# GoPiGo_Proto_10.net
KiCad netlist of a schematic drawn in EAGLE
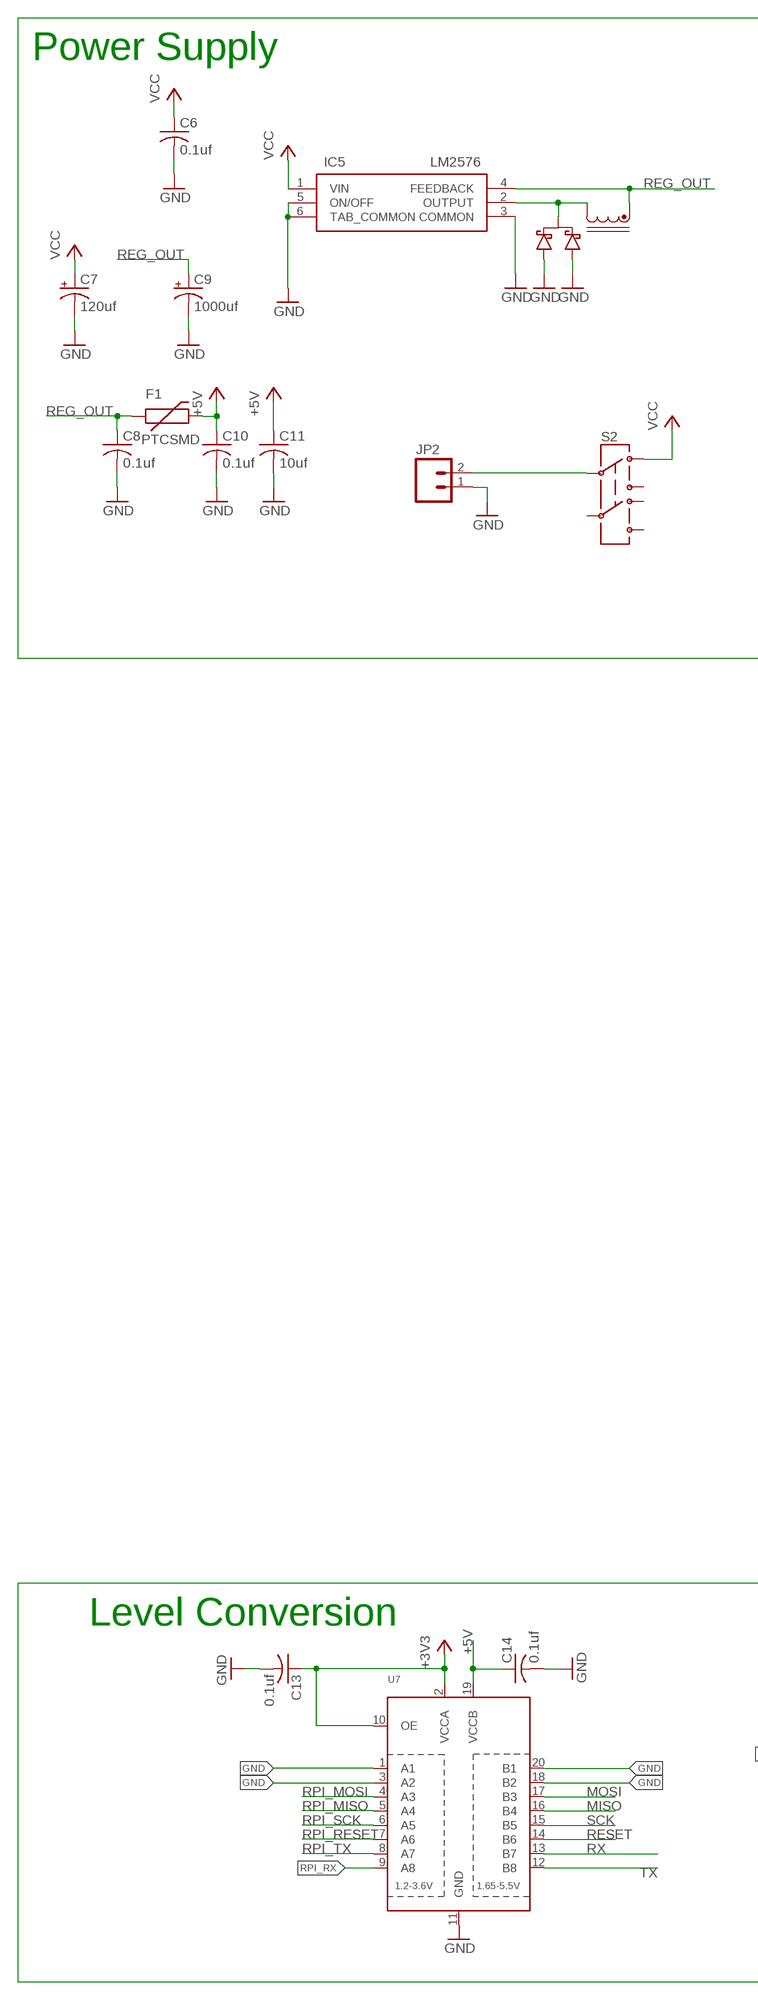
[diagram p0: schematic, sheet 1, part 1 of 2]
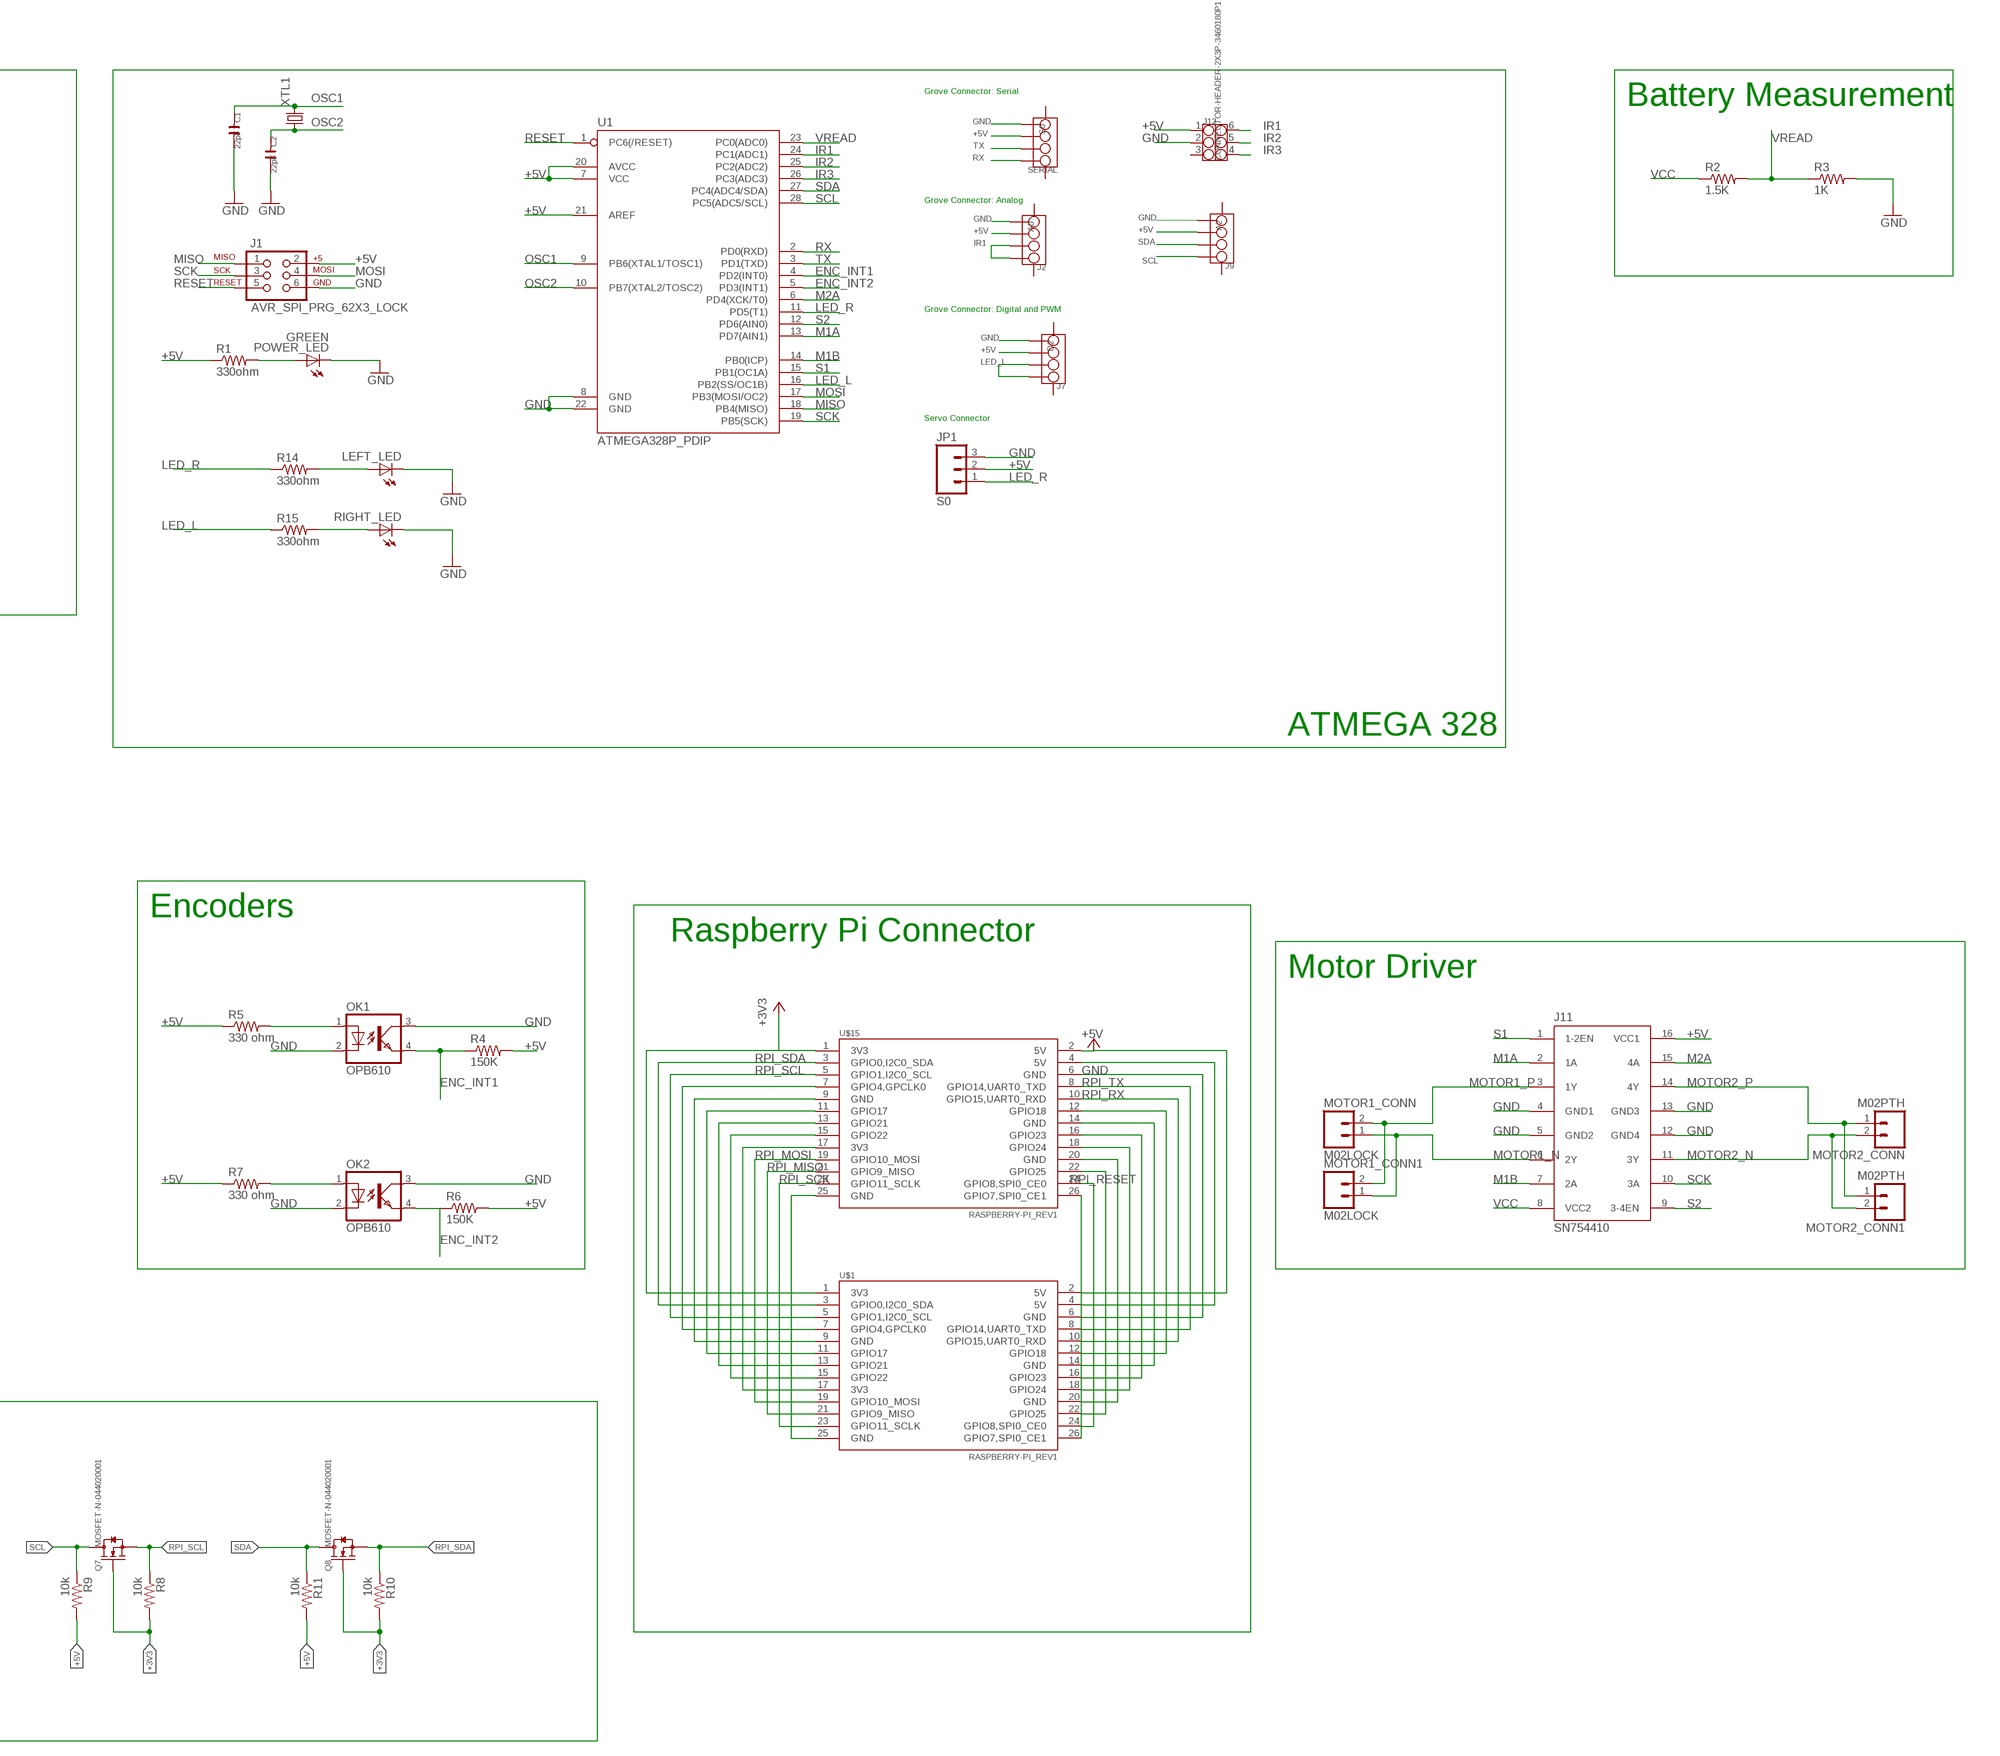
[diagram p1: schematic, sheet 1, part 2 of 2]

(export (version "E")
  (design (tool "Eeschema 10.0.6"))
  (components
    (comp (ref "C1")
      (value "22pF")
      (footprint "eagle-import:C0805")
      (libsource (lib "eagle-import") (part "C-0805"))
    )
    (comp (ref "C2")
      (value "22pF")
      (footprint "eagle-import:C0805")
      (libsource (lib "eagle-import") (part "C-0805"))
    )
    (comp (ref "C6")
      (value "0.1uf")
      (footprint "eagle-import:C0603")
      (libsource (lib "eagle-import") (part "resistor_C-USC0603"))
    )
    (comp (ref "C7")
      (value "120uf")
      (footprint "eagle-import:E2,5-6")
      (libsource (lib "eagle-import") (part "CPOL-USE2.5-6"))
    )
    (comp (ref "C8")
      (value "0.1uf")
      (footprint "eagle-import:C0603")
      (libsource (lib "eagle-import") (part "resistor_C-USC0603"))
    )
    (comp (ref "C9")
      (value "1000uf")
      (footprint "eagle-import:E5-13")
      (libsource (lib "eagle-import") (part "CPOL-USE5-13"))
    )
    (comp (ref "C10")
      (value "0.1uf")
      (footprint "eagle-import:C0603")
      (libsource (lib "eagle-import") (part "resistor_C-USC0603"))
    )
    (comp (ref "C11")
      (value "10uf")
      (footprint "eagle-import:C0805")
      (libsource (lib "eagle-import") (part "C-USC0805"))
    )
    (comp (ref "C13")
      (value "0.1uf")
      (footprint "eagle-import:C0603")
      (libsource (lib "eagle-import") (part "resistor_C-USC0603"))
    )
    (comp (ref "C14")
      (value "0.1uf")
      (footprint "eagle-import:C0603")
      (libsource (lib "eagle-import") (part "resistor_C-USC0603"))
    )
    (comp (ref "D1")
      (value "DIODE_SCHOTTKY_VS-6CWQ04FNTRPBF")
      (footprint "eagle-import:DPAK")
      (libsource (lib "eagle-import") (part "DIODE_SCHOTTKY_VS-6CWQ04FNTRPBF"))
    )
    (comp (ref "F1")
      (value "PTCSMD")
      (footprint "eagle-import:PTC-1206")
      (libsource (lib "eagle-import") (part "PTCSMD"))
    )
    (comp (ref "IC5")
      (value "LM2576")
      (footprint "eagle-import:TO220-5-H")
      (libsource (lib "eagle-import") (part "REGULATOR_SWITCHING_LM2575_LM2576"))
    )
    (comp (ref "J1")
      (value "AVR_SPI_PRG_62X3_LOCK")
      (footprint "eagle-import:2X3_LOCK")
      (libsource (lib "eagle-import") (part "AVR_SPI_PRG_62X3_LOCK"))
    )
    (comp (ref "J2")
      (value "A0")
      (footprint "eagle-import:4P-SMD-2.0-90D")
      (libsource (lib "eagle-import") (part "GROVE-4P-2.0-SMD-FEMALE-REINFORCE-3470120P1"))
    )
    (comp (ref "J7")
      (value "D2")
      (footprint "eagle-import:4P-SMD-2.0-90D")
      (libsource (lib "eagle-import") (part "GROVE-4P-2.0-SMD-FEMALE-REINFORCE-3470120P1"))
    )
    (comp (ref "J9")
      (value "A2")
      (footprint "eagle-import:4P-SMD-2.0-90D")
      (libsource (lib "eagle-import") (part "GROVE-4P-2.0-SMD-FEMALE-REINFORCE-3470120P1"))
    )
    (comp (ref "J11")
      (value "SN754410")
      (footprint "eagle-import:DIL16")
      (fields (field (name "MPN") "L293D"))
      (libsource (lib "eagle-import") (part "L293D"))
    )
    (comp (ref "J12")
      (value "CONNECTOR-HEADER-2X3P-3460180P1")
      (footprint "eagle-import:2X3P-2.54-2.54-11.6-3.0-BLACK-MALE")
      (libsource (lib "eagle-import") (part "CONNECTOR-HEADER-2X3P-3460180P1"))
    )
    (comp (ref "JP1")
      (value "S0")
      (footprint "eagle-import:1X03")
      (libsource (lib "eagle-import") (part "M03PTH"))
    )
    (comp (ref "JP2")
      (value "M02LOCK")
      (footprint "eagle-import:1X02_LOCK")
      (libsource (lib "eagle-import") (part "zz SparkFun_M02LOCK"))
    )
    (comp (ref "LEFT_LED")
      (value "LED5MM")
      (footprint "eagle-import:LED5MM")
      (libsource (lib "eagle-import") (part "LED5MM"))
    )
    (comp (ref "MOTOR1_CONN")
      (value "M02LOCK")
      (footprint "eagle-import:1X02_LOCK")
      (libsource (lib "eagle-import") (part "M02LOCK"))
    )
    (comp (ref "MOTOR1_CONN1")
      (value "M02LOCK")
      (footprint "eagle-import:1X02_LOCK")
      (libsource (lib "eagle-import") (part "M02LOCK"))
    )
    (comp (ref "MOTOR2_CONN")
      (value "M02PTH")
      (footprint "eagle-import:1X02")
      (libsource (lib "eagle-import") (part "M02PTH"))
    )
    (comp (ref "MOTOR2_CONN1")
      (value "M02PTH")
      (footprint "eagle-import:1X02")
      (libsource (lib "eagle-import") (part "M02PTH"))
    )
    (comp (ref "OK1")
      (value "OPB610")
      (footprint "eagle-import:SFH9310")
      (libsource (lib "eagle-import") (part "SFH9310"))
    )
    (comp (ref "OK2")
      (value "OPB610")
      (footprint "eagle-import:SFH9310")
      (libsource (lib "eagle-import") (part "SFH9310"))
    )
    (comp (ref "POWER_LED")
      (value "GREEN")
      (footprint "eagle-import:LED-0603")
      (libsource (lib "eagle-import") (part "LED-GREEN0603"))
    )
    (comp (ref "Q7")
      (value "MOSFET-N-044020001")
      (footprint "eagle-import:SOT23")
      (libsource (lib "eagle-import") (part "MOSFET-N-044020001"))
    )
    (comp (ref "Q8")
      (value "MOSFET-N-044020001")
      (footprint "eagle-import:SOT23")
      (libsource (lib "eagle-import") (part "MOSFET-N-044020001"))
    )
    (comp (ref "R1")
      (value "330ohm")
      (footprint "eagle-import:0603-RES")
      (libsource (lib "eagle-import") (part "RESISTOR0603"))
    )
    (comp (ref "R2")
      (value "1.5K")
      (footprint "eagle-import:0603-RES")
      (libsource (lib "eagle-import") (part "RESISTOR0603"))
    )
    (comp (ref "R3")
      (value "1K")
      (footprint "eagle-import:0603-RES")
      (libsource (lib "eagle-import") (part "RESISTOR0603"))
    )
    (comp (ref "R4")
      (value "150K")
      (footprint "eagle-import:0603-RES")
      (libsource (lib "eagle-import") (part "RESISTOR0603"))
    )
    (comp (ref "R5")
      (value "330 ohm")
      (footprint "eagle-import:0603-RES")
      (libsource (lib "eagle-import") (part "RESISTOR0603"))
    )
    (comp (ref "R6")
      (value "150K")
      (footprint "eagle-import:0603-RES")
      (libsource (lib "eagle-import") (part "RESISTOR0603"))
    )
    (comp (ref "R7")
      (value "330 ohm")
      (footprint "eagle-import:0603-RES")
      (libsource (lib "eagle-import") (part "RESISTOR0603"))
    )
    (comp (ref "R8")
      (value "10k")
      (footprint "eagle-import:0603-RES")
      (libsource (lib "eagle-import") (part "RESISTOR0603"))
    )
    (comp (ref "R9")
      (value "10k")
      (footprint "eagle-import:0603-RES")
      (libsource (lib "eagle-import") (part "RESISTOR0603"))
    )
    (comp (ref "R10")
      (value "10k")
      (footprint "eagle-import:0603-RES")
      (libsource (lib "eagle-import") (part "RESISTOR0603"))
    )
    (comp (ref "R11")
      (value "10k")
      (footprint "eagle-import:0603-RES")
      (libsource (lib "eagle-import") (part "RESISTOR0603"))
    )
    (comp (ref "R14")
      (value "330ohm")
      (footprint "eagle-import:0603-RES")
      (libsource (lib "eagle-import") (part "RESISTOR0603"))
    )
    (comp (ref "R15")
      (value "330ohm")
      (footprint "eagle-import:0603-RES")
      (libsource (lib "eagle-import") (part "RESISTOR0603"))
    )
    (comp (ref "RIGHT_LED")
      (value "LED5MM")
      (footprint "eagle-import:LED5MM")
      (libsource (lib "eagle-import") (part "LED5MM"))
    )
    (comp (ref "S2")
      (value "SWITCH-DPDTOS")
      (footprint "eagle-import:OS")
      (libsource (lib "eagle-import") (part "SWITCH-DPDTOS"))
    )
    (comp (ref "SERIAL")
      (value "S0")
      (footprint "eagle-import:4P-SMD-2.0-90D")
      (libsource (lib "eagle-import") (part "GROVE-4P-2.0-SMD-FEMALE-REINFORCE-3470120P1"))
    )
    (comp (ref "U$1")
      (value "RASPBERRY-PI_REV1")
      (footprint "eagle-import:RASPBERRY-PI_REV1")
      (libsource (lib "eagle-import") (part "RASPBERRY-PI_REV1"))
    )
    (comp (ref "U$14")
      (value "INDUCTOR_PULSE_P0250.XXXNL")
      (footprint "eagle-import:INDUCTOR_PULSE_P0250.XXXNL")
      (libsource (lib "eagle-import") (part "INDUCTOR_PULSE_P0250.XXXNL"))
    )
    (comp (ref "U$15")
      (value "RASPBERRY-PI_REV1")
      (footprint "eagle-import:RASPBERRY-PI_REV1")
      (libsource (lib "eagle-import") (part "RASPBERRY-PI_REV1"))
    )
    (comp (ref "U1")
      (value "ATMEGA328P_PDIP")
      (footprint "eagle-import:DIL28-3")
      (libsource (lib "eagle-import") (part "ATMEGA328P_PDIP"))
    )
    (comp (ref "U7")
      (value "TXB0108PWR")
      (footprint "eagle-import:TSSOP20")
      (libsource (lib "eagle-import") (part "TXB0108PWR"))
    )
    (comp (ref "XTL1")
      (value "CRYSTALHC49S")
      (footprint "eagle-import:HC49_S")
      (libsource (lib "eagle-import") (part "CRYSTALHC49S"))
    )
  )
  (nets
    (net (code "1") (name "+3V3") (class "Default")
      (node (ref "C13") (pin "1") (pinfunction "1_1") (pintype "passive"))
      (node (ref "Q7") (pin "1") (pinfunction "G_1") (pintype "passive"))
      (node (ref "Q8") (pin "1") (pinfunction "G_1") (pintype "passive"))
      (node (ref "R10") (pin "2") (pinfunction "2_2") (pintype "passive"))
      (node (ref "R8") (pin "2") (pinfunction "2_2") (pintype "passive"))
      (node (ref "U$1") (pin "1") (pinfunction "3V3_1") (pintype "bidirectional"))
      (node (ref "U$15") (pin "1") (pinfunction "3V3_1") (pintype "bidirectional"))
      (node (ref "U7") (pin "10") (pinfunction "OE_10") (pintype "bidirectional"))
      (node (ref "U7") (pin "2") (pinfunction "VCCA_2") (pintype "bidirectional"))
    )
    (net (code "2") (name "+5V") (class "Default")
      (node (ref "C10") (pin "1") (pinfunction "1_1") (pintype "passive"))
      (node (ref "C11") (pin "1") (pinfunction "1_1") (pintype "passive"))
      (node (ref "C14") (pin "1") (pinfunction "1_1") (pintype "passive"))
      (node (ref "F1") (pin "2") (pinfunction "2_2") (pintype "bidirectional"))
      (node (ref "J1") (pin "2") (pinfunction "2_2") (pintype "passive"))
      (node (ref "J11") (pin "16") (pinfunction "VCC1_16") (pintype "power_in"))
      (node (ref "J12") (pin "1") (pinfunction "1_1") (pintype "bidirectional"))
      (node (ref "J2") (pin "3") (pinfunction "3_3") (pintype "bidirectional"))
      (node (ref "J7") (pin "3") (pinfunction "3_3") (pintype "bidirectional"))
      (node (ref "J9") (pin "3") (pinfunction "3_3") (pintype "bidirectional"))
      (node (ref "JP1") (pin "2") (pinfunction "2_2") (pintype "passive"))
      (node (ref "R1") (pin "1") (pinfunction "1_1") (pintype "passive"))
      (node (ref "R11") (pin "2") (pinfunction "2_2") (pintype "passive"))
      (node (ref "R4") (pin "2") (pinfunction "2_2") (pintype "passive"))
      (node (ref "R5") (pin "1") (pinfunction "1_1") (pintype "passive"))
      (node (ref "R6") (pin "2") (pinfunction "2_2") (pintype "passive"))
      (node (ref "R7") (pin "1") (pinfunction "1_1") (pintype "passive"))
      (node (ref "R9") (pin "2") (pinfunction "2_2") (pintype "passive"))
      (node (ref "SERIAL") (pin "3") (pinfunction "3_3") (pintype "bidirectional"))
      (node (ref "U$1") (pin "2") (pinfunction "5V_2") (pintype "bidirectional"))
      (node (ref "U$15") (pin "2") (pinfunction "5V_2") (pintype "bidirectional"))
      (node (ref "U1") (pin "20") (pinfunction "AVCC_20") (pintype "bidirectional"))
      (node (ref "U1") (pin "21") (pinfunction "AREF_21") (pintype "bidirectional"))
      (node (ref "U1") (pin "7") (pinfunction "VCC_7") (pintype "bidirectional"))
      (node (ref "U7") (pin "19") (pinfunction "VCCB_19") (pintype "bidirectional"))
    )
    (net (code "3") (name "/ENC_INT1") (class "Default")
      (node (ref "OK1") (pin "4") (pinfunction "EMIT_4") (pintype "passive"))
      (node (ref "R4") (pin "1") (pinfunction "1_1") (pintype "passive"))
      (node (ref "U1") (pin "4") (pinfunction "PD2(INT0)_4") (pintype "bidirectional"))
    )
    (net (code "4") (name "/ENC_INT2") (class "Default")
      (node (ref "OK2") (pin "4") (pinfunction "EMIT_4") (pintype "passive"))
      (node (ref "R6") (pin "1") (pinfunction "1_1") (pintype "passive"))
      (node (ref "U1") (pin "5") (pinfunction "PD3(INT1)_5") (pintype "bidirectional"))
    )
    (net (code "5") (name "/IR1") (class "Default")
      (node (ref "J12") (pin "6") (pinfunction "6_6") (pintype "bidirectional"))
      (node (ref "J2") (pin "1") (pinfunction "1_1") (pintype "bidirectional"))
      (node (ref "J2") (pin "2") (pinfunction "2_2") (pintype "bidirectional"))
      (node (ref "U1") (pin "24") (pinfunction "PC1(ADC1)_24") (pintype "bidirectional"))
    )
    (net (code "6") (name "/IR2") (class "Default")
      (node (ref "J12") (pin "5") (pinfunction "5_5") (pintype "bidirectional"))
      (node (ref "U1") (pin "25") (pinfunction "PC2(ADC2)_25") (pintype "bidirectional"))
    )
    (net (code "7") (name "/IR3") (class "Default")
      (node (ref "J12") (pin "4") (pinfunction "4_4") (pintype "bidirectional"))
      (node (ref "U1") (pin "26") (pinfunction "PC3(ADC3)_26") (pintype "bidirectional"))
    )
    (net (code "8") (name "/LED_L") (class "Default")
      (node (ref "J7") (pin "1") (pinfunction "1_1") (pintype "bidirectional"))
      (node (ref "J7") (pin "2") (pinfunction "2_2") (pintype "bidirectional"))
      (node (ref "R15") (pin "1") (pinfunction "1_1") (pintype "passive"))
      (node (ref "U1") (pin "16") (pinfunction "PB2(SS/OC1B)_16") (pintype "bidirectional"))
    )
    (net (code "9") (name "/LED_R") (class "Default")
      (node (ref "JP1") (pin "1") (pinfunction "1_1") (pintype "passive"))
      (node (ref "R14") (pin "1") (pinfunction "1_1") (pintype "passive"))
      (node (ref "U1") (pin "11") (pinfunction "PD5(T1)_11") (pintype "bidirectional"))
    )
    (net (code "10") (name "/M1A") (class "Default")
      (node (ref "J11") (pin "2") (pinfunction "1A_2") (pintype "input"))
      (node (ref "U1") (pin "13") (pinfunction "PD7(AIN1)_13") (pintype "bidirectional"))
    )
    (net (code "11") (name "/M1B") (class "Default")
      (node (ref "J11") (pin "7") (pinfunction "2A_7") (pintype "input"))
      (node (ref "U1") (pin "14") (pinfunction "PB0(ICP)_14") (pintype "bidirectional"))
    )
    (net (code "12") (name "/M2A") (class "Default")
      (node (ref "J11") (pin "15") (pinfunction "4A_15") (pintype "input"))
      (node (ref "U1") (pin "6") (pinfunction "PD4(XCK/T0)_6") (pintype "bidirectional"))
    )
    (net (code "13") (name "/MISO") (class "Default")
      (node (ref "J1") (pin "1") (pinfunction "1_1") (pintype "passive"))
      (node (ref "U1") (pin "18") (pinfunction "PB4(MISO)_18") (pintype "bidirectional"))
      (node (ref "U7") (pin "16") (pinfunction "B4_16") (pintype "bidirectional"))
    )
    (net (code "14") (name "/MOSI") (class "Default")
      (node (ref "J1") (pin "4") (pinfunction "4_4") (pintype "passive"))
      (node (ref "U1") (pin "17") (pinfunction "PB3(MOSI/OC2)_17") (pintype "bidirectional"))
      (node (ref "U7") (pin "17") (pinfunction "B3_17") (pintype "bidirectional"))
    )
    (net (code "15") (name "/MOTOR1_N") (class "Default")
      (node (ref "J11") (pin "6") (pinfunction "2Y_6") (pintype "output"))
      (node (ref "MOTOR1_CONN") (pin "1") (pinfunction "1_1") (pintype "passive"))
      (node (ref "MOTOR1_CONN1") (pin "1") (pinfunction "1_1") (pintype "passive"))
    )
    (net (code "16") (name "/MOTOR1_P") (class "Default")
      (node (ref "J11") (pin "3") (pinfunction "1Y_3") (pintype "output"))
      (node (ref "MOTOR1_CONN") (pin "2") (pinfunction "2_2") (pintype "passive"))
      (node (ref "MOTOR1_CONN1") (pin "2") (pinfunction "2_2") (pintype "passive"))
    )
    (net (code "17") (name "/MOTOR2_N") (class "Default")
      (node (ref "J11") (pin "11") (pinfunction "3Y_11") (pintype "output"))
      (node (ref "MOTOR2_CONN") (pin "2") (pinfunction "2_2") (pintype "passive"))
      (node (ref "MOTOR2_CONN1") (pin "2") (pinfunction "2_2") (pintype "passive"))
    )
    (net (code "18") (name "/MOTOR2_P") (class "Default")
      (node (ref "J11") (pin "14") (pinfunction "4Y_14") (pintype "output"))
      (node (ref "MOTOR2_CONN") (pin "1") (pinfunction "1_1") (pintype "passive"))
      (node (ref "MOTOR2_CONN1") (pin "1") (pinfunction "1_1") (pintype "passive"))
    )
    (net (code "19") (name "/OSC1") (class "Default")
      (node (ref "C1") (pin "1") (pinfunction "1_1") (pintype "bidirectional"))
      (node (ref "U1") (pin "9") (pinfunction "PB6(XTAL1/TOSC1)_9") (pintype "bidirectional"))
      (node (ref "XTL1") (pin "2") (pinfunction "2_2") (pintype "passive"))
    )
    (net (code "20") (name "/OSC2") (class "Default")
      (node (ref "C2") (pin "1") (pinfunction "1_1") (pintype "bidirectional"))
      (node (ref "U1") (pin "10") (pinfunction "PB7(XTAL2/TOSC2)_10") (pintype "bidirectional"))
      (node (ref "XTL1") (pin "1") (pinfunction "1_1") (pintype "passive"))
    )
    (net (code "21") (name "/REG_OUT") (class "Default")
      (node (ref "C8") (pin "1") (pinfunction "1_1") (pintype "passive"))
      (node (ref "C9") (pin "+") (pinfunction "+_+") (pintype "passive"))
      (node (ref "F1") (pin "1") (pinfunction "1_1") (pintype "bidirectional"))
      (node (ref "IC5") (pin "4") (pinfunction "FEEDBACK_4") (pintype "bidirectional"))
      (node (ref "U$14") (pin "P$1") (pinfunction "P$1_P$1") (pintype "bidirectional"))
    )
    (net (code "22") (name "/RESET") (class "Default")
      (node (ref "J1") (pin "5") (pinfunction "5_5") (pintype "passive"))
      (node (ref "U1") (pin "1") (pinfunction "PC6(/RESET)_1") (pintype "bidirectional"))
      (node (ref "U7") (pin "14") (pinfunction "B6_14") (pintype "bidirectional"))
    )
    (net (code "23") (name "/RPI_MISO") (class "Default")
      (node (ref "U$1") (pin "21") (pinfunction "GPIO9_MISO_21") (pintype "bidirectional"))
      (node (ref "U$15") (pin "21") (pinfunction "GPIO9_MISO_21") (pintype "bidirectional"))
      (node (ref "U7") (pin "5") (pinfunction "A4_5") (pintype "bidirectional"))
    )
    (net (code "24") (name "/RPI_MOSI") (class "Default")
      (node (ref "U$1") (pin "19") (pinfunction "GPIO10_MOSI_19") (pintype "bidirectional"))
      (node (ref "U$15") (pin "19") (pinfunction "GPIO10_MOSI_19") (pintype "bidirectional"))
      (node (ref "U7") (pin "4") (pinfunction "A3_4") (pintype "bidirectional"))
    )
    (net (code "25") (name "/RPI_RESET") (class "Default")
      (node (ref "U$1") (pin "24") (pinfunction "GPIO8,SPI0_CE0_24") (pintype "bidirectional"))
      (node (ref "U$15") (pin "24") (pinfunction "GPIO8,SPI0_CE0_24") (pintype "bidirectional"))
      (node (ref "U7") (pin "7") (pinfunction "A6_7") (pintype "bidirectional"))
    )
    (net (code "26") (name "/RPI_SCK") (class "Default")
      (node (ref "U$1") (pin "23") (pinfunction "GPIO11_SCLK_23") (pintype "bidirectional"))
      (node (ref "U$15") (pin "23") (pinfunction "GPIO11_SCLK_23") (pintype "bidirectional"))
      (node (ref "U7") (pin "6") (pinfunction "A5_6") (pintype "bidirectional"))
    )
    (net (code "27") (name "/RPI_TX") (class "Default")
      (node (ref "U$1") (pin "8") (pinfunction "GPIO14,UART0_TXD_8") (pintype "bidirectional"))
      (node (ref "U$15") (pin "8") (pinfunction "GPIO14,UART0_TXD_8") (pintype "bidirectional"))
      (node (ref "U7") (pin "8") (pinfunction "A7_8") (pintype "bidirectional"))
    )
    (net (code "28") (name "/RX") (class "Default")
      (node (ref "SERIAL") (pin "1") (pinfunction "1_1") (pintype "bidirectional"))
      (node (ref "U1") (pin "2") (pinfunction "PD0(RXD)_2") (pintype "bidirectional"))
      (node (ref "U7") (pin "13") (pinfunction "B7_13") (pintype "bidirectional"))
    )
    (net (code "29") (name "/S1") (class "Default")
      (node (ref "J11") (pin "1") (pinfunction "1-2EN_1") (pintype "input"))
      (node (ref "U1") (pin "15") (pinfunction "PB1(OC1A)_15") (pintype "bidirectional"))
    )
    (net (code "30") (name "/S2") (class "Default")
      (node (ref "J11") (pin "9") (pinfunction "3-4EN_9") (pintype "input"))
      (node (ref "U1") (pin "12") (pinfunction "PD6(AIN0)_12") (pintype "bidirectional"))
    )
    (net (code "31") (name "/SCK") (class "Default")
      (node (ref "J1") (pin "3") (pinfunction "3_3") (pintype "passive"))
      (node (ref "J11") (pin "10") (pinfunction "3A_10") (pintype "input"))
      (node (ref "U1") (pin "19") (pinfunction "PB5(SCK)_19") (pintype "bidirectional"))
      (node (ref "U7") (pin "15") (pinfunction "B5_15") (pintype "bidirectional"))
    )
    (net (code "32") (name "/TX") (class "Default")
      (node (ref "SERIAL") (pin "2") (pinfunction "2_2") (pintype "bidirectional"))
      (node (ref "U1") (pin "3") (pinfunction "PD1(TXD)_3") (pintype "bidirectional"))
      (node (ref "U7") (pin "12") (pinfunction "B8_12") (pintype "bidirectional"))
    )
    (net (code "33") (name "/VREAD") (class "Default")
      (node (ref "R2") (pin "2") (pinfunction "2_2") (pintype "passive"))
      (node (ref "R3") (pin "1") (pinfunction "1_1") (pintype "passive"))
      (node (ref "U1") (pin "23") (pinfunction "PC0(ADC0)_23") (pintype "bidirectional"))
    )
    (net (code "34") (name "GND") (class "Default")
      (node (ref "C1") (pin "2") (pinfunction "2_2") (pintype "bidirectional"))
      (node (ref "C10") (pin "2") (pinfunction "2_2") (pintype "passive"))
      (node (ref "C11") (pin "2") (pinfunction "2_2") (pintype "passive"))
      (node (ref "C13") (pin "2") (pinfunction "2_2") (pintype "passive"))
      (node (ref "C14") (pin "2") (pinfunction "2_2") (pintype "passive"))
      (node (ref "C2") (pin "2") (pinfunction "2_2") (pintype "bidirectional"))
      (node (ref "C6") (pin "2") (pinfunction "2_2") (pintype "passive"))
      (node (ref "C7") (pin "-") (pinfunction "-_-") (pintype "passive"))
      (node (ref "C8") (pin "2") (pinfunction "2_2") (pintype "passive"))
      (node (ref "C9") (pin "-") (pinfunction "-_-") (pintype "passive"))
      (node (ref "D1") (pin "1") (pinfunction "P$1_1") (pintype "bidirectional"))
      (node (ref "D1") (pin "3") (pinfunction "P$3_3") (pintype "bidirectional"))
      (node (ref "IC5") (pin "3") (pinfunction "COMMON_3") (pintype "bidirectional"))
      (node (ref "IC5") (pin "5") (pinfunction "ON/OFF_5") (pintype "bidirectional"))
      (node (ref "IC5") (pin "6") (pinfunction "TAB_COMMON_6") (pintype "bidirectional"))
      (node (ref "J1") (pin "6") (pinfunction "6_6") (pintype "passive"))
      (node (ref "J11") (pin "12") (pinfunction "GND4_12") (pintype "power_in"))
      (node (ref "J11") (pin "13") (pinfunction "GND3_13") (pintype "power_in"))
      (node (ref "J11") (pin "4") (pinfunction "GND1_4") (pintype "power_in"))
      (node (ref "J11") (pin "5") (pinfunction "GND2_5") (pintype "power_in"))
      (node (ref "J12") (pin "2") (pinfunction "2_2") (pintype "bidirectional"))
      (node (ref "J2") (pin "4") (pinfunction "4_4") (pintype "bidirectional"))
      (node (ref "J7") (pin "4") (pinfunction "4_4") (pintype "bidirectional"))
      (node (ref "J9") (pin "4") (pinfunction "4_4") (pintype "bidirectional"))
      (node (ref "JP1") (pin "3") (pinfunction "3_3") (pintype "passive"))
      (node (ref "JP2") (pin "1") (pinfunction "1_1") (pintype "passive"))
      (node (ref "LEFT_LED") (pin "K") (pinfunction "C_K") (pintype "passive"))
      (node (ref "OK1") (pin "2") (pinfunction "C_2") (pintype "passive"))
      (node (ref "OK1") (pin "3") (pinfunction "COL_3") (pintype "passive"))
      (node (ref "OK2") (pin "2") (pinfunction "C_2") (pintype "passive"))
      (node (ref "OK2") (pin "3") (pinfunction "COL_3") (pintype "passive"))
      (node (ref "POWER_LED") (pin "C") (pinfunction "C_C") (pintype "passive"))
      (node (ref "R3") (pin "2") (pinfunction "2_2") (pintype "passive"))
      (node (ref "RIGHT_LED") (pin "K") (pinfunction "C_K") (pintype "passive"))
      (node (ref "SERIAL") (pin "4") (pinfunction "4_4") (pintype "bidirectional"))
      (node (ref "U$1") (pin "6") (pinfunction "GND_6") (pintype "bidirectional"))
      (node (ref "U$15") (pin "6") (pinfunction "GND_6") (pintype "bidirectional"))
      (node (ref "U1") (pin "22") (pinfunction "GND_22") (pintype "bidirectional"))
      (node (ref "U1") (pin "8") (pinfunction "GND_8") (pintype "bidirectional"))
      (node (ref "U7") (pin "1") (pinfunction "A1_1") (pintype "bidirectional"))
      (node (ref "U7") (pin "11") (pinfunction "GND_11") (pintype "bidirectional"))
      (node (ref "U7") (pin "18") (pinfunction "B2_18") (pintype "bidirectional"))
      (node (ref "U7") (pin "20") (pinfunction "B1_20") (pintype "bidirectional"))
      (node (ref "U7") (pin "3") (pinfunction "A2_3") (pintype "bidirectional"))
    )
    (net (code "35") (name "Net-(D1-P$2)") (class "Default")
      (node (ref "D1") (pin "4") (pinfunction "P$2_4") (pintype "bidirectional"))
      (node (ref "IC5") (pin "2") (pinfunction "OUTPUT_2") (pintype "bidirectional"))
      (node (ref "U$14") (pin "P$2") (pinfunction "P$2_P$2") (pintype "bidirectional"))
    )
    (net (code "36") (name "Net-(JP2-Pad2)") (class "Default")
      (node (ref "JP2") (pin "2") (pinfunction "2_2") (pintype "passive"))
      (node (ref "S2") (pin "2") (pinfunction "2_2") (pintype "bidirectional"))
    )
    (net (code "37") (name "Net-(LEFT_LED-PadA)") (class "Default")
      (node (ref "LEFT_LED") (pin "A") (pinfunction "A_A") (pintype "passive"))
      (node (ref "R14") (pin "2") (pinfunction "2_2") (pintype "passive"))
    )
    (net (code "38") (name "Net-(OK1-A)") (class "Default")
      (node (ref "OK1") (pin "1") (pinfunction "A_1") (pintype "passive"))
      (node (ref "R5") (pin "2") (pinfunction "2_2") (pintype "passive"))
    )
    (net (code "39") (name "Net-(OK2-A)") (class "Default")
      (node (ref "OK2") (pin "1") (pinfunction "A_1") (pintype "passive"))
      (node (ref "R7") (pin "2") (pinfunction "2_2") (pintype "passive"))
    )
    (net (code "40") (name "Net-(POWER_LED-PadA)") (class "Default")
      (node (ref "POWER_LED") (pin "A") (pinfunction "A_A") (pintype "passive"))
      (node (ref "R1") (pin "2") (pinfunction "2_2") (pintype "passive"))
    )
    (net (code "41") (name "Net-(R15-Pad2)") (class "Default")
      (node (ref "R15") (pin "2") (pinfunction "2_2") (pintype "passive"))
      (node (ref "RIGHT_LED") (pin "A") (pinfunction "A_A") (pintype "passive"))
    )
    (net (code "42") (name "Net-(U$1-3V3-Pad17)") (class "Default")
      (node (ref "U$1") (pin "17") (pinfunction "3V3_17") (pintype "bidirectional"))
      (node (ref "U$15") (pin "17") (pinfunction "3V3_17") (pintype "bidirectional"))
    )
    (net (code "43") (name "Net-(U$1-5V-Pad4)") (class "Default")
      (node (ref "U$1") (pin "4") (pinfunction "5V_4") (pintype "bidirectional"))
      (node (ref "U$15") (pin "4") (pinfunction "5V_4") (pintype "bidirectional"))
    )
    (net (code "44") (name "Net-(U$1-GND-Pad9)") (class "Default")
      (node (ref "U$1") (pin "9") (pinfunction "GND_9") (pintype "bidirectional"))
      (node (ref "U$15") (pin "9") (pinfunction "GND_9") (pintype "bidirectional"))
    )
    (net (code "45") (name "Net-(U$1-GND-Pad14)") (class "Default")
      (node (ref "U$1") (pin "14") (pinfunction "GND_14") (pintype "bidirectional"))
      (node (ref "U$15") (pin "14") (pinfunction "GND_14") (pintype "bidirectional"))
    )
    (net (code "46") (name "Net-(U$1-GND-Pad20)") (class "Default")
      (node (ref "U$1") (pin "20") (pinfunction "GND_20") (pintype "bidirectional"))
      (node (ref "U$15") (pin "20") (pinfunction "GND_20") (pintype "bidirectional"))
    )
    (net (code "47") (name "Net-(U$1-GND-Pad25)") (class "Default")
      (node (ref "U$1") (pin "25") (pinfunction "GND_25") (pintype "bidirectional"))
      (node (ref "U$15") (pin "25") (pinfunction "GND_25") (pintype "bidirectional"))
    )
    (net (code "48") (name "Net-(U$1-GPIO4,GPCLK0)") (class "Default")
      (node (ref "U$1") (pin "7") (pinfunction "GPIO4,GPCLK0_7") (pintype "bidirectional"))
      (node (ref "U$15") (pin "7") (pinfunction "GPIO4,GPCLK0_7") (pintype "bidirectional"))
    )
    (net (code "49") (name "Net-(U$1-GPIO7,SPI0_CE1)") (class "Default")
      (node (ref "U$1") (pin "26") (pinfunction "GPIO7,SPI0_CE1_26") (pintype "bidirectional"))
      (node (ref "U$15") (pin "26") (pinfunction "GPIO7,SPI0_CE1_26") (pintype "bidirectional"))
    )
    (net (code "50") (name "Net-(U$1-GPIO17)") (class "Default")
      (node (ref "U$1") (pin "11") (pinfunction "GPIO17_11") (pintype "bidirectional"))
      (node (ref "U$15") (pin "11") (pinfunction "GPIO17_11") (pintype "bidirectional"))
    )
    (net (code "51") (name "Net-(U$1-GPIO18)") (class "Default")
      (node (ref "U$1") (pin "12") (pinfunction "GPIO18_12") (pintype "bidirectional"))
      (node (ref "U$15") (pin "12") (pinfunction "GPIO18_12") (pintype "bidirectional"))
    )
    (net (code "52") (name "Net-(U$1-GPIO21)") (class "Default")
      (node (ref "U$1") (pin "13") (pinfunction "GPIO21_13") (pintype "bidirectional"))
      (node (ref "U$15") (pin "13") (pinfunction "GPIO21_13") (pintype "bidirectional"))
    )
    (net (code "53") (name "Net-(U$1-GPIO22)") (class "Default")
      (node (ref "U$1") (pin "15") (pinfunction "GPIO22_15") (pintype "bidirectional"))
      (node (ref "U$15") (pin "15") (pinfunction "GPIO22_15") (pintype "bidirectional"))
    )
    (net (code "54") (name "Net-(U$1-GPIO23)") (class "Default")
      (node (ref "U$1") (pin "16") (pinfunction "GPIO23_16") (pintype "bidirectional"))
      (node (ref "U$15") (pin "16") (pinfunction "GPIO23_16") (pintype "bidirectional"))
    )
    (net (code "55") (name "Net-(U$1-GPIO24)") (class "Default")
      (node (ref "U$1") (pin "18") (pinfunction "GPIO24_18") (pintype "bidirectional"))
      (node (ref "U$15") (pin "18") (pinfunction "GPIO24_18") (pintype "bidirectional"))
    )
    (net (code "56") (name "Net-(U$1-GPIO25)") (class "Default")
      (node (ref "U$1") (pin "22") (pinfunction "GPIO25_22") (pintype "bidirectional"))
      (node (ref "U$15") (pin "22") (pinfunction "GPIO25_22") (pintype "bidirectional"))
    )
    (net (code "57") (name "RPI_RX") (class "Default")
      (node (ref "U$1") (pin "10") (pinfunction "GPIO15,UART0_RXD_10") (pintype "bidirectional"))
      (node (ref "U$15") (pin "10") (pinfunction "GPIO15,UART0_RXD_10") (pintype "bidirectional"))
      (node (ref "U7") (pin "9") (pinfunction "A8_9") (pintype "bidirectional"))
    )
    (net (code "58") (name "RPI_SCL") (class "Default")
      (node (ref "Q7") (pin "2") (pinfunction "S_2") (pintype "passive"))
      (node (ref "R8") (pin "1") (pinfunction "1_1") (pintype "passive"))
      (node (ref "U$1") (pin "5") (pinfunction "GPIO1,I2C0_SCL_5") (pintype "bidirectional"))
      (node (ref "U$15") (pin "5") (pinfunction "GPIO1,I2C0_SCL_5") (pintype "bidirectional"))
    )
    (net (code "59") (name "RPI_SDA") (class "Default")
      (node (ref "Q8") (pin "2") (pinfunction "S_2") (pintype "passive"))
      (node (ref "R10") (pin "1") (pinfunction "1_1") (pintype "passive"))
      (node (ref "U$1") (pin "3") (pinfunction "GPIO0,I2C0_SDA_3") (pintype "bidirectional"))
      (node (ref "U$15") (pin "3") (pinfunction "GPIO0,I2C0_SDA_3") (pintype "bidirectional"))
    )
    (net (code "60") (name "SCL") (class "Default")
      (node (ref "J9") (pin "1") (pinfunction "1_1") (pintype "bidirectional"))
      (node (ref "Q7") (pin "3") (pinfunction "D_3") (pintype "passive"))
      (node (ref "R9") (pin "1") (pinfunction "1_1") (pintype "passive"))
      (node (ref "U1") (pin "28") (pinfunction "PC5(ADC5/SCL)_28") (pintype "bidirectional"))
    )
    (net (code "61") (name "SDA") (class "Default")
      (node (ref "J9") (pin "2") (pinfunction "2_2") (pintype "bidirectional"))
      (node (ref "Q8") (pin "3") (pinfunction "D_3") (pintype "passive"))
      (node (ref "R11") (pin "1") (pinfunction "1_1") (pintype "passive"))
      (node (ref "U1") (pin "27") (pinfunction "PC4(ADC4/SDA)_27") (pintype "bidirectional"))
    )
    (net (code "62") (name "VCC") (class "Default")
      (node (ref "C6") (pin "1") (pinfunction "1_1") (pintype "passive"))
      (node (ref "C7") (pin "+") (pinfunction "+_+") (pintype "passive"))
      (node (ref "IC5") (pin "1") (pinfunction "VIN_1") (pintype "bidirectional"))
      (node (ref "J11") (pin "8") (pinfunction "VCC2_8") (pintype "power_in"))
      (node (ref "R2") (pin "1") (pinfunction "1_1") (pintype "passive"))
      (node (ref "S2") (pin "1") (pinfunction "1_1") (pintype "bidirectional"))
    )
    (net (code "63") (name "unconnected-(J2-PadSS1)") (class "Default")
      (node (ref "J2") (pin "SS1") (pinfunction "SS1_SS1") (pintype "bidirectional"))
    )
    (net (code "64") (name "unconnected-(J2-PadSS2)") (class "Default")
      (node (ref "J2") (pin "SS2") (pinfunction "SS2_SS2") (pintype "bidirectional"))
    )
    (net (code "65") (name "unconnected-(J7-PadSS1)") (class "Default")
      (node (ref "J7") (pin "SS1") (pinfunction "SS1_SS1") (pintype "bidirectional"))
    )
    (net (code "66") (name "unconnected-(J7-PadSS2)") (class "Default")
      (node (ref "J7") (pin "SS2") (pinfunction "SS2_SS2") (pintype "bidirectional"))
    )
    (net (code "67") (name "unconnected-(J9-PadSS1)") (class "Default")
      (node (ref "J9") (pin "SS1") (pinfunction "SS1_SS1") (pintype "bidirectional"))
    )
    (net (code "68") (name "unconnected-(J9-PadSS2)") (class "Default")
      (node (ref "J9") (pin "SS2") (pinfunction "SS2_SS2") (pintype "bidirectional"))
    )
    (net (code "69") (name "unconnected-(J12-Pad3)") (class "Default")
      (node (ref "J12") (pin "3") (pinfunction "3_3") (pintype "bidirectional"))
    )
    (net (code "70") (name "unconnected-(S2-Pad3)") (class "Default")
      (node (ref "S2") (pin "3") (pinfunction "3_3") (pintype "bidirectional"))
    )
    (net (code "71") (name "unconnected-(S2-Pad4)") (class "Default")
      (node (ref "S2") (pin "4") (pinfunction "4_4") (pintype "bidirectional"))
    )
    (net (code "72") (name "unconnected-(S2-Pad5)") (class "Default")
      (node (ref "S2") (pin "5") (pinfunction "5_5") (pintype "bidirectional"))
    )
    (net (code "73") (name "unconnected-(S2-Pad6)") (class "Default")
      (node (ref "S2") (pin "6") (pinfunction "6_6") (pintype "bidirectional"))
    )
    (net (code "74") (name "unconnected-(SERIAL-PadSS1)") (class "Default")
      (node (ref "SERIAL") (pin "SS1") (pinfunction "SS1_SS1") (pintype "bidirectional"))
    )
    (net (code "75") (name "unconnected-(SERIAL-PadSS2)") (class "Default")
      (node (ref "SERIAL") (pin "SS2") (pinfunction "SS2_SS2") (pintype "bidirectional"))
    )
  )
)
